# Photocoupler12Vinput.net
KiCad netlist of a schematic drawn in Altium Designer
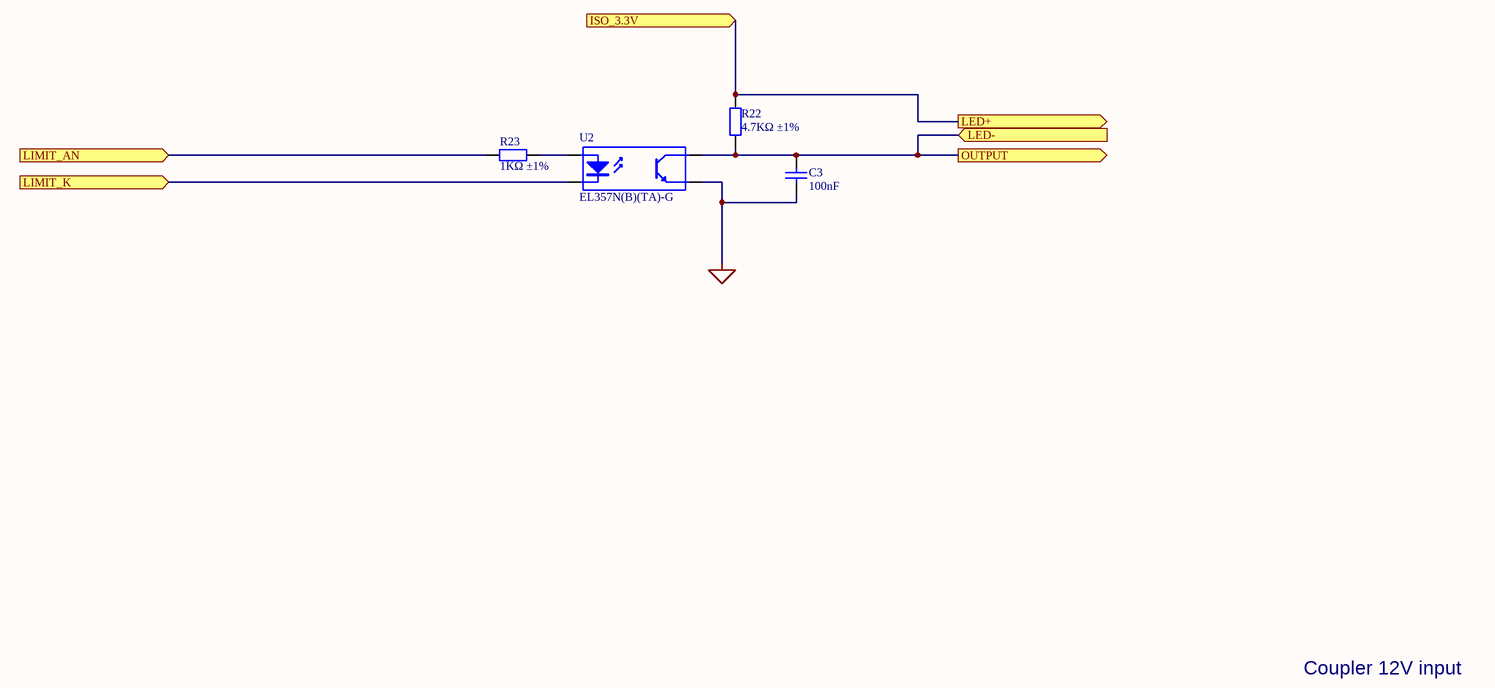
[diagram p0: Photocoupler12Vinput.SchDoc]

(export (version "E")
  (design (tool "Eeschema 10.0.6"))
  (components
    (comp (ref "C3")
      (value "100nF")
      (footprint "0402_C")
      (description "16V 100nF X7R ±10% 0402 Multilayer Ceramic Capacitors MLCC - SMD/SMT ROHS")
      (fields (field (name "MANUFACTURER") "Samsung Electro-Mechanics") (field (name "TOLERANCE") "10%"))
      (libsource (lib "Sienci_Labs") (part "0402 100nF (104) 10% 16V"))
    )
    (comp (ref "R22")
      (value "4.7KΩ ±1%")
      (footprint "0402_R")
      (description "Chip resistor")
      (fields
        (field (name "MANUFACTURER") "Uniroyal Elec")
        (field (name "MANUFACTURER PART NUMBER") "0402WGF4701TCE")
      )
      (libsource (lib "Sienci_Labs") (part "0402 4.7K (4701) 1%"))
    )
    (comp (ref "R23")
      (value "1KΩ ±1%")
      (footprint "0603_R")
      (description "Chip resistor")
      (fields
        (field (name "MANUFACTURER") "Uniroyal Elec")
        (field (name "MANUFACTURER PART NUMBER") "0603WAF1001T5E")
      )
      (libsource (lib "Sienci_Labs") (part "0603 1K (1001) 1%"))
    )
    (comp (ref "U2")
      (value "EL357N(B)(TA)-G")
      (footprint "Miscellaneous Devices LC:SOP-4_P2.54")
      (description "Optocoupler SOP-4, EL357N(B)(TA)-G, Everlight Electronics")
      (fields (field (name "MANUFACTURER") "Everlight"))
      (libsource (lib "Sienci_Labs") (part "EL357N(B)(TA)-G_[C6649]"))
    )
  )
  (nets
    (net (code "1") (name "/ISO_3.3V") (class "Default")
      (node (ref "R22") (pin "2") (pinfunction "2_2") (pintype "passive"))
    )
    (net (code "2") (name "/LED-") (class "Default")
      (node (ref "C3") (pin "2") (pinfunction "2_2") (pintype "passive"))
      (node (ref "R22") (pin "1") (pinfunction "1_1") (pintype "passive"))
      (node (ref "U2") (pin "4") (pinfunction "C_4") (pintype "passive"))
    )
    (net (code "3") (name "/LIMIT_AN") (class "Default")
      (node (ref "R23") (pin "1") (pinfunction "1_1") (pintype "passive"))
    )
    (net (code "4") (name "/LIMIT_K") (class "Default")
      (node (ref "U2") (pin "2") (pinfunction "K_2") (pintype "passive"))
    )
    (net (code "5") (name "MCU_GND") (class "Default")
      (node (ref "C3") (pin "1") (pinfunction "1_1") (pintype "passive"))
      (node (ref "U2") (pin "3") (pinfunction "E_3") (pintype "passive"))
    )
    (net (code "6") (name "Net-(U2-A)") (class "Default")
      (node (ref "R23") (pin "2") (pinfunction "2_2") (pintype "passive"))
      (node (ref "U2") (pin "1") (pinfunction "A_1") (pintype "passive"))
    )
  )
)
